# PCB_Board2.net
KiCad netlist of a schematic drawn in Altium Designer
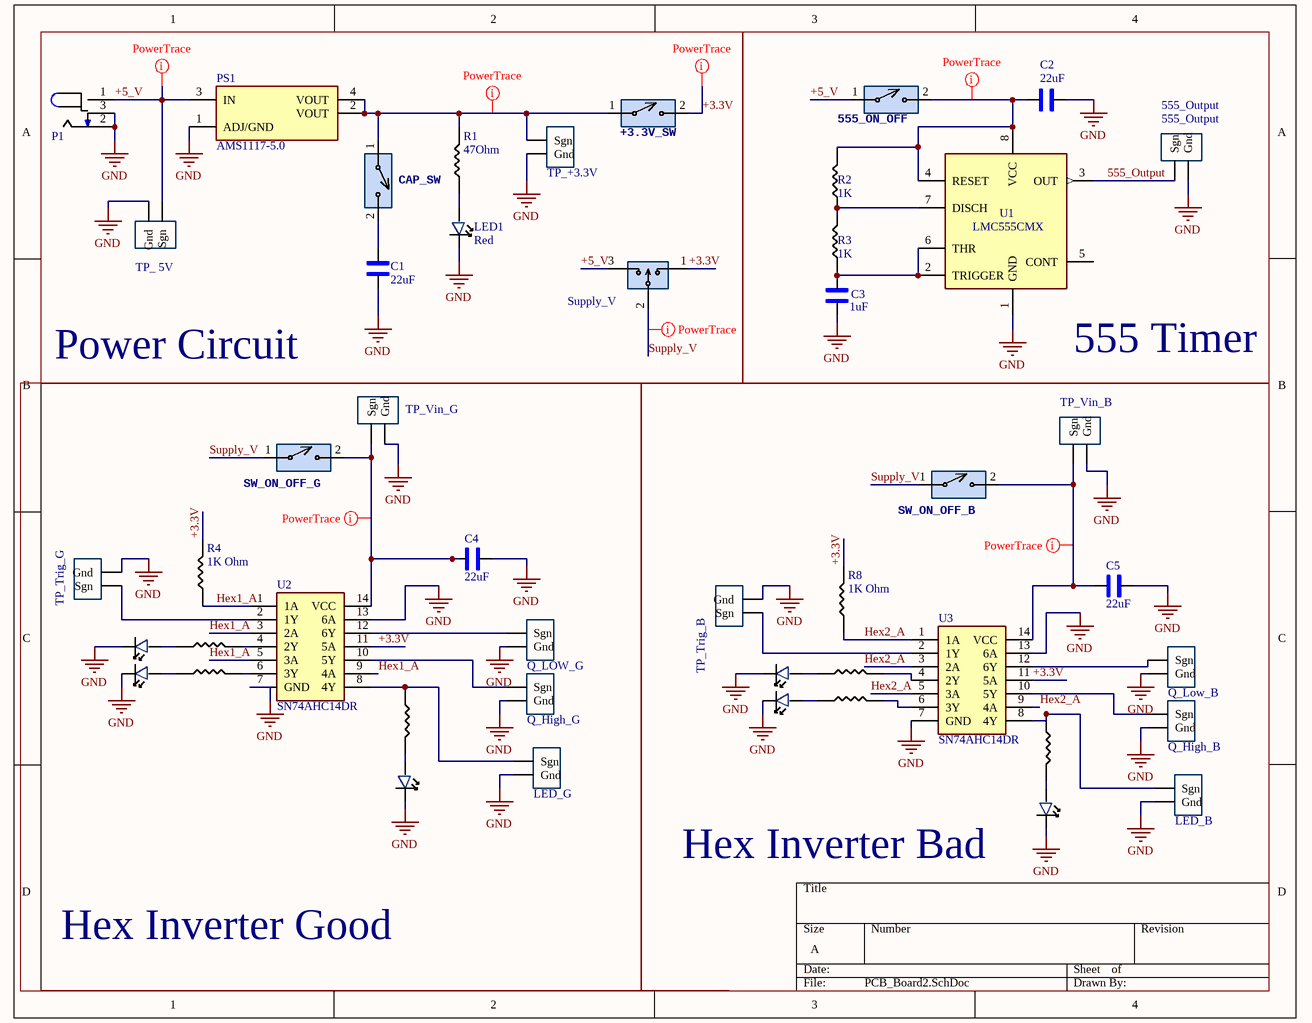
[diagram p0: PCB_Board2.SchDoc]

(export (version "E")
  (design (tool "Eeschema 10.0.6"))
  (components
    (comp (ref "+3.3V_SW")
      (value "SW_2Pin_100mil_Switch")
      (footprint "2Pin-Header-Conn")
      (description "2Pin Header")
      (fields (field (name "LCSC PART#") "C124375"))
      (libsource (lib "ECEN5730Lib_2023_05_DS") (part "SW_2Pin_100mil_Switch"))
    )
    (comp (ref "555_ON_OFF")
      (value "SW_2Pin_100mil_Switch")
      (footprint "2Pin-Header-Conn")
      (description "2Pin Header")
      (fields (field (name "LCSC PART#") "C124375"))
      (libsource (lib "ECEN5730Lib_2023_05_DS") (part "SW_2Pin_100mil_Switch"))
    )
    (comp (ref "555_Output")
      (value "555_Output")
      (footprint "TP10x_Probe")
      (description "Test Point 300 mil centers")
      (libsource (lib "") (part "TP_10x_Probe_2"))
    )
    (comp (ref "C1")
      (value "22uF")
      (footprint "1206_Passive_Capacitor")
      (description "22uF ±10% 25V X5R 1206 Multilayer Ceramic Capacitors MLCC - SMD/SMT RoHS")
      (fields (field (name "MFR PART #") "CL31A226KAHNNNE") (field (name "LCSC PART#") "C12891"))
      (libsource (lib "ECEN5730Lib_2023_05_DS") (part "C_22uF_1206"))
    )
    (comp (ref "C2")
      (value "22uF")
      (footprint "1206_Passive_Capacitor")
      (description "22uF ±10% 25V X5R 1206 Multilayer Ceramic Capacitors MLCC - SMD/SMT RoHS")
      (fields (field (name "MFR PART #") "CL31A226KAHNNNE") (field (name "LCSC PART#") "C12891"))
      (libsource (lib "ECEN5730Lib_2023_05_DS") (part "C_22uF_1206"))
    )
    (comp (ref "C3")
      (value "1uF")
      (footprint "1206_Passive_Capacitor")
      (description "MULTILAYER CERAMIC CAPACITORS MLCC - SMD/SMT 1UF 50V 1206 ROHS")
      (fields (field (name "MFR PART #") "CL31B105KBHNNNE") (field (name "LCSC PART#") "C1848"))
      (libsource (lib "ECEN5730Lib_2023_05_DS") (part "C_1uF_1206"))
    )
    (comp (ref "C4")
      (value "22uF")
      (footprint "1206_Passive_Capacitor")
      (description "22uF ±10% 25V X5R 1206 Multilayer Ceramic Capacitors MLCC - SMD/SMT RoHS")
      (fields (field (name "MFR PART #") "CL31A226KAHNNNE") (field (name "LCSC PART#") "C12891"))
      (libsource (lib "ECEN5730Lib_2023_05_DS") (part "C_22uF_1206"))
    )
    (comp (ref "C5")
      (value "22uF")
      (footprint "1206_Passive_Capacitor")
      (description "22uF ±10% 25V X5R 1206 Multilayer Ceramic Capacitors MLCC - SMD/SMT RoHS")
      (fields (field (name "MFR PART #") "CL31A226KAHNNNE") (field (name "LCSC PART#") "C12891"))
      (libsource (lib "ECEN5730Lib_2023_05_DS") (part "C_22uF_1206"))
    )
    (comp (ref "CAP_SW")
      (value "SW_2Pin_100mil_Switch")
      (footprint "2Pin-Header-Conn")
      (description "2Pin Header")
      (fields (field (name "LCSC PART#") "C124375"))
      (libsource (lib "") (part "SW_2Pin_100mil_Switch_1"))
    )
    (comp (ref "LED1")
      (value "Red")
      (footprint "LED_1206")
      (description "Red 621~631nm 1206 Light Emitting Diodes (LED) RoHS")
      (fields (field (name "MFR PART #") "15-21/R6C-FQ1R1B/2T") (field (name "LCSC PART#") "C93133"))
      (libsource (lib "ECEN5730Lib_2023_05_DS") (part "LED_RED_1206"))
    )
    (comp (ref "LED2")
      (value "Red")
      (footprint "LED_1206")
      (description "Red 621~631nm 1206 Light Emitting Diodes (LED) RoHS")
      (fields (field (name "MFR PART #") "15-21/R6C-FQ1R1B/2T") (field (name "LCSC PART#") "C93133"))
      (libsource (lib "ECEN5730Lib_2023_05_DS") (part "LED_RED_1206"))
    )
    (comp (ref "LED3")
      (value "Red")
      (footprint "LED_1206")
      (description "Red 621~631nm 1206 Light Emitting Diodes (LED) RoHS")
      (fields (field (name "MFR PART #") "15-21/R6C-FQ1R1B/2T") (field (name "LCSC PART#") "C93133"))
      (libsource (lib "ECEN5730Lib_2023_05_DS") (part "LED_RED_1206"))
    )
    (comp (ref "LED4")
      (value "Red")
      (footprint "LED_1206")
      (description "Red 621~631nm 1206 Light Emitting Diodes (LED) RoHS")
      (fields (field (name "MFR PART #") "15-21/R6C-FQ1R1B/2T") (field (name "LCSC PART#") "C93133"))
      (libsource (lib "ECEN5730Lib_2023_05_DS") (part "LED_RED_1206"))
    )
    (comp (ref "LED5")
      (value "Red")
      (footprint "LED_1206")
      (description "Red 621~631nm 1206 Light Emitting Diodes (LED) RoHS")
      (fields (field (name "MFR PART #") "15-21/R6C-FQ1R1B/2T") (field (name "LCSC PART#") "C93133"))
      (libsource (lib "ECEN5730Lib_2023_05_DS") (part "LED_RED_1206"))
    )
    (comp (ref "LED6")
      (value "Red")
      (footprint "LED_1206")
      (description "Red 621~631nm 1206 Light Emitting Diodes (LED) RoHS")
      (fields (field (name "MFR PART #") "15-21/R6C-FQ1R1B/2T") (field (name "LCSC PART#") "C93133"))
      (libsource (lib "ECEN5730Lib_2023_05_DS") (part "LED_RED_1206"))
    )
    (comp (ref "LED7")
      (value "Red")
      (footprint "LED_1206")
      (description "Red 621~631nm 1206 Light Emitting Diodes (LED) RoHS")
      (fields (field (name "MFR PART #") "15-21/R6C-FQ1R1B/2T") (field (name "LCSC PART#") "C93133"))
      (libsource (lib "ECEN5730Lib_2023_05_DS") (part "LED_RED_1206"))
    )
    (comp (ref "LED_B")
      (value "10x Probe TP")
      (footprint "TP10x_Probe")
      (description "Test Point 300 mil centers")
      (libsource (lib "ECEN5730Lib_2023_05_DS") (part "TP_10x_Probe"))
    )
    (comp (ref "LED_G")
      (value "10x Probe TP")
      (footprint "TP10x_Probe")
      (description "Test Point 300 mil centers")
      (libsource (lib "ECEN5730Lib_2023_05_DS") (part "TP_10x_Probe"))
    )
    (comp (ref "P1")
      (value "Power Jack")
      (footprint "Power_Jack")
      (description "Power Barrel Connector Jack 2.10mm ID (0.083\"), 5.50mm OD (0.217\") Through Hole, Right Angle")
      (fields (field (name "MFR PART #") "PJ-102A") (field (name "LCSC PART#") "C136744"))
      (libsource (lib "ECEN5730Lib_2023_05_DS") (part "P_Power Jack"))
    )
    (comp (ref "PS1")
      (value "AMS1117-5.0")
      (footprint "LDO")
      (description "LOW DROPOUT REGULATORS(LDO) POSITIVE FIXED 1.3V @ 1A 15V 5V 1A SOT-223 ROHS")
      (fields (field (name "LCSC PART#") "C6187"))
      (libsource (lib "ECEN5730Lib_2023_05_DS") (part "PS_AMS_LDO_5V"))
    )
    (comp (ref "Q_High_B")
      (value "10x Probe TP")
      (footprint "TP10x_Probe")
      (description "Test Point 300 mil centers")
      (libsource (lib "ECEN5730Lib_2023_05_DS") (part "TP_10x_Probe"))
    )
    (comp (ref "Q_High_G")
      (value "10x Probe TP")
      (footprint "TP10x_Probe")
      (description "Test Point 300 mil centers")
      (libsource (lib "ECEN5730Lib_2023_05_DS") (part "TP_10x_Probe"))
    )
    (comp (ref "Q_Low_B")
      (value "10x Probe TP")
      (footprint "TP10x_Probe")
      (description "Test Point 300 mil centers")
      (libsource (lib "ECEN5730Lib_2023_05_DS") (part "TP_10x_Probe"))
    )
    (comp (ref "Q_LOW_G")
      (value "10x Probe TP")
      (footprint "TP10x_Probe")
      (description "Test Point 300 mil centers")
      (libsource (lib "ECEN5730Lib_2023_05_DS") (part "TP_10x_Probe"))
    )
    (comp (ref "R1")
      (value "47Ohm")
      (footprint "1206_Passive_Resitor")
      (description "47Ω ±5% 0.25W ±200ppm/℃ 1206 Chip Resistor - Surface Mount RoHS")
      (fields (field (name "MFR PART #") "1206W4J0470T5E") (field (name "LCSC PART#") "C25384"))
      (libsource (lib "ECEN5730Lib_2023_05_DS") (part "R_47Ohm_1206"))
    )
    (comp (ref "R2")
      (value "1K")
      (footprint "1206_Passive_Resitor")
      (description "CHIP RESISTOR - SURFACE MOUNT 1KOHMS ±1% 1/4W 1206 ROHS")
      (fields (field (name "MFR PART #") "RNCP1206FTD1K00CT") (field (name "LCSC PART#") "C4410"))
      (libsource (lib "ECEN5730Lib_2023_05_DS") (part "R_1K_1206"))
    )
    (comp (ref "R3")
      (value "1K")
      (footprint "1206_Passive_Resitor")
      (description "CHIP RESISTOR - SURFACE MOUNT 1KOHMS ±1% 1/4W 1206 ROHS")
      (fields (field (name "MFR PART #") "RNCP1206FTD1K00CT") (field (name "LCSC PART#") "C4410"))
      (libsource (lib "ECEN5730Lib_2023_05_DS") (part "R_1K_1206"))
    )
    (comp (ref "R4")
      (value "1K Ohm")
      (footprint "1206_Passive_Resitor")
      (description "CHIP RESISTOR - SURFACE MOUNT 1KOHMS ±1% 1/4W 1206 ROHS")
      (fields (field (name "MFR PART #") "RNCP1206FTD1K00CT") (field (name "LCSC PART#") "C4410"))
      (libsource (lib "ECEN5730Lib_2023_05_DS") (part "R_1K_1206"))
    )
    (comp (ref "R5")
      (value "2Ohm")
      (footprint "1206_Passive_Resitor")
      (description "2Ω ±1% 0.25W ±400ppm/℃ 1206 Chip Resistor - Surface Mount RoHS")
      (fields (field (name "MFR PART #") "1206W4F200KT5E") (field (name "LCSC PART#") "C17942"))
      (libsource (lib "ECEN5730Lib_2023_05_DS") (part "R_2Ohm_1206"))
    )
    (comp (ref "R6")
      (value "2Ohm")
      (footprint "1206_Passive_Resitor")
      (description "2Ω ±1% 0.25W ±400ppm/℃ 1206 Chip Resistor - Surface Mount RoHS")
      (fields (field (name "MFR PART #") "1206W4F200KT5E") (field (name "LCSC PART#") "C17942"))
      (libsource (lib "ECEN5730Lib_2023_05_DS") (part "R_2Ohm_1206"))
    )
    (comp (ref "R7")
      (value "2Ohm")
      (footprint "1206_Passive_Resitor")
      (description "2Ω ±1% 0.25W ±400ppm/℃ 1206 Chip Resistor - Surface Mount RoHS")
      (fields (field (name "MFR PART #") "1206W4F200KT5E") (field (name "LCSC PART#") "C17942"))
      (libsource (lib "ECEN5730Lib_2023_05_DS") (part "R_2Ohm_1206"))
    )
    (comp (ref "R8")
      (value "1K Ohm")
      (footprint "1206_Passive_Resitor")
      (description "CHIP RESISTOR - SURFACE MOUNT 1KOHMS ±1% 1/4W 1206 ROHS")
      (fields (field (name "MFR PART #") "RNCP1206FTD1K00CT") (field (name "LCSC PART#") "C4410"))
      (libsource (lib "ECEN5730Lib_2023_05_DS") (part "R_1K_1206"))
    )
    (comp (ref "R9")
      (value "2Ohm")
      (footprint "1206_Passive_Resitor")
      (description "2Ω ±1% 0.25W ±400ppm/℃ 1206 Chip Resistor - Surface Mount RoHS")
      (fields (field (name "MFR PART #") "1206W4F200KT5E") (field (name "LCSC PART#") "C17942"))
      (libsource (lib "ECEN5730Lib_2023_05_DS") (part "R_2Ohm_1206"))
    )
    (comp (ref "R10")
      (value "2Ohm")
      (footprint "1206_Passive_Resitor")
      (description "2Ω ±1% 0.25W ±400ppm/℃ 1206 Chip Resistor - Surface Mount RoHS")
      (fields (field (name "MFR PART #") "1206W4F200KT5E") (field (name "LCSC PART#") "C17942"))
      (libsource (lib "ECEN5730Lib_2023_05_DS") (part "R_2Ohm_1206"))
    )
    (comp (ref "R11")
      (value "2Ohm")
      (footprint "1206_Passive_Resitor")
      (description "2Ω ±1% 0.25W ±400ppm/℃ 1206 Chip Resistor - Surface Mount RoHS")
      (fields (field (name "MFR PART #") "1206W4F200KT5E") (field (name "LCSC PART#") "C17942"))
      (libsource (lib "ECEN5730Lib_2023_05_DS") (part "R_2Ohm_1206"))
    )
    (comp (ref "Supply_V")
      (value "PREC003SAAN-RC")
      (footprint "3_PIN_100mil")
      (description "Connector Header Through Hole 3 position 0.100\" (2.54mm)")
      (fields (field (name "LCSC PART#") "C49257"))
      (libsource (lib "ECEN5730Lib_2023_05_DS") (part "SW_3Pin_100mil_Switch"))
    )
    (comp (ref "SW_ON_OFF_B")
      (value "SW_2Pin_100mil_Switch")
      (footprint "2Pin-Header-Conn")
      (description "2Pin Header")
      (fields (field (name "LCSC PART#") "C124375"))
      (libsource (lib "ECEN5730Lib_2023_05_DS") (part "SW_2Pin_100mil_Switch"))
    )
    (comp (ref "SW_ON_OFF_G")
      (value "SW_2Pin_100mil_Switch")
      (footprint "2Pin-Header-Conn")
      (description "2Pin Header")
      (fields (field (name "LCSC PART#") "C124375"))
      (libsource (lib "ECEN5730Lib_2023_05_DS") (part "SW_2Pin_100mil_Switch"))
    )
    (comp (ref "TP_ 5V")
      (value "10x Probe TP")
      (footprint "TP10x_Probe")
      (description "Test Point 300 mil centers")
      (libsource (lib "") (part "TP_10x_Probe_1"))
    )
    (comp (ref "TP_+3.3V")
      (value "10x Probe TP")
      (footprint "TP10x_Probe")
      (description "Test Point 300 mil centers")
      (libsource (lib "ECEN5730Lib_2023_05_DS") (part "TP_10x_Probe"))
    )
    (comp (ref "TP_Trig_B")
      (value "10x Probe TP")
      (footprint "TP10x_Probe")
      (description "Test Point 300 mil centers")
      (libsource (lib "") (part "TP_10x_Probe_3"))
    )
    (comp (ref "TP_Trig_G")
      (value "10x Probe TP")
      (footprint "TP10x_Probe")
      (description "Test Point 300 mil centers")
      (libsource (lib "") (part "TP_10x_Probe_3"))
    )
    (comp (ref "TP_Vin_B")
      (value "10x Probe TP")
      (footprint "TP10x_Probe")
      (description "Test Point 300 mil centers")
      (libsource (lib "") (part "TP_10x_Probe_2"))
    )
    (comp (ref "TP_Vin_G")
      (value "10x Probe TP")
      (footprint "TP10x_Probe")
      (description "Test Point 300 mil centers")
      (libsource (lib "") (part "TP_10x_Probe_2"))
    )
    (comp (ref "U1")
      (value "LMC555CMX")
      (footprint "TS555IDTTR")
      (description "555 Type, Timer/Oscillator _Single_ IC 3MHz 8-SO")
      (fields (field (name "MFR PART #") "LMC555CMX/NOPB") (field (name "LCSC PART#") "C90760"))
      (libsource (lib "ECEN5730Lib_2023_05_DS") (part "U_555_Fast"))
    )
    (comp (ref "U2")
      (value "SN74AHC14DR")
      (footprint "HEX_74AC14")
      (description "Inverter IC 6 Channel Schmitt Trigger 14-SOIC")
      (fields (field (name "LCSC PART#") "C6942"))
      (libsource (lib "ECEN5730Lib_2023_05_DS") (part "U_74AHC14"))
    )
    (comp (ref "U3")
      (value "SN74AHC14DR")
      (footprint "HEX_74AC14")
      (description "Inverter IC 6 Channel Schmitt Trigger 14-SOIC")
      (fields (field (name "LCSC PART#") "C6942"))
      (libsource (lib "ECEN5730Lib_2023_05_DS") (part "U_74AHC14"))
    )
  )
  (nets
    (net (code "1") (name "/+3.3V") (class "Default")
      (node (ref "+3.3V_SW") (pin "2") (pinfunction "2_2") (pintype "passive"))
      (node (ref "R4") (pin "2") (pinfunction "2_2") (pintype "passive"))
      (node (ref "R8") (pin "2") (pinfunction "2_2") (pintype "passive"))
      (node (ref "Supply_V") (pin "1") (pinfunction "1_1") (pintype "passive"))
      (node (ref "U2") (pin "11") (pinfunction "5A_11") (pintype "passive"))
      (node (ref "U3") (pin "11") (pinfunction "5A_11") (pintype "passive"))
    )
    (net (code "2") (name "/+5_V") (class "Default")
      (node (ref "555_ON_OFF") (pin "1") (pinfunction "1_1") (pintype "passive"))
      (node (ref "P1") (pin "1") (pinfunction "1_1") (pintype "power_in"))
      (node (ref "PS1") (pin "3") (pinfunction "IN_3") (pintype "power_in"))
      (node (ref "Supply_V") (pin "3") (pinfunction "3_3") (pintype "passive"))
      (node (ref "TP_ 5V") (pin "1") (pinfunction "Sgn_1") (pintype "passive"))
    )
    (net (code "3") (name "/555_Output") (class "Default")
      (node (ref "555_Output") (pin "1") (pinfunction "Sgn_1") (pintype "passive"))
      (node (ref "U1") (pin "3") (pinfunction "OUT_3") (pintype "output"))
    )
    (net (code "4") (name "/Hex1_A") (class "Default")
      (node (ref "R4") (pin "1") (pinfunction "1_1") (pintype "passive"))
      (node (ref "U2") (pin "1") (pinfunction "1A_1") (pintype "passive"))
      (node (ref "U2") (pin "3") (pinfunction "2A_3") (pintype "passive"))
      (node (ref "U2") (pin "5") (pinfunction "3A_5") (pintype "passive"))
      (node (ref "U2") (pin "9") (pinfunction "4A_9") (pintype "passive"))
    )
    (net (code "5") (name "/Hex2_A") (class "Default")
      (node (ref "R8") (pin "1") (pinfunction "1_1") (pintype "passive"))
      (node (ref "U3") (pin "1") (pinfunction "1A_1") (pintype "passive"))
      (node (ref "U3") (pin "3") (pinfunction "2A_3") (pintype "passive"))
      (node (ref "U3") (pin "5") (pinfunction "3A_5") (pintype "passive"))
      (node (ref "U3") (pin "9") (pinfunction "4A_9") (pintype "passive"))
    )
    (net (code "6") (name "/Supply_V") (class "Default")
      (node (ref "SW_ON_OFF_B") (pin "1") (pinfunction "1_1") (pintype "passive"))
      (node (ref "SW_ON_OFF_G") (pin "1") (pinfunction "1_1") (pintype "passive"))
      (node (ref "Supply_V") (pin "2") (pinfunction "2_2") (pintype "passive"))
    )
    (net (code "7") (name "GND") (class "Default")
      (node (ref "555_Output") (pin "2") (pinfunction "Gnd_2") (pintype "passive"))
      (node (ref "C1") (pin "1") (pinfunction "1_1") (pintype "passive"))
      (node (ref "C2") (pin "2") (pinfunction "2_2") (pintype "passive"))
      (node (ref "C3") (pin "2") (pinfunction "2_2") (pintype "passive"))
      (node (ref "C4") (pin "1") (pinfunction "1_1") (pintype "passive"))
      (node (ref "C5") (pin "1") (pinfunction "1_1") (pintype "passive"))
      (node (ref "LED1") (pin "2") (pinfunction "2_2") (pintype "passive"))
      (node (ref "LED2") (pin "2") (pinfunction "2_2") (pintype "passive"))
      (node (ref "LED3") (pin "2") (pinfunction "2_2") (pintype "passive"))
      (node (ref "LED4") (pin "2") (pinfunction "2_2") (pintype "passive"))
      (node (ref "LED5") (pin "2") (pinfunction "2_2") (pintype "passive"))
      (node (ref "LED6") (pin "2") (pinfunction "2_2") (pintype "passive"))
      (node (ref "LED7") (pin "2") (pinfunction "2_2") (pintype "passive"))
      (node (ref "LED_B") (pin "2") (pinfunction "Gnd_2") (pintype "passive"))
      (node (ref "LED_G") (pin "2") (pinfunction "Gnd_2") (pintype "passive"))
      (node (ref "P1") (pin "2") (pinfunction "2_2") (pintype "power_in"))
      (node (ref "P1") (pin "3") (pinfunction "3_3") (pintype "power_in"))
      (node (ref "PS1") (pin "1") (pinfunction "ADJ/GND_1") (pintype "passive"))
      (node (ref "Q_High_B") (pin "2") (pinfunction "Gnd_2") (pintype "passive"))
      (node (ref "Q_High_G") (pin "2") (pinfunction "Gnd_2") (pintype "passive"))
      (node (ref "Q_LOW_G") (pin "2") (pinfunction "Gnd_2") (pintype "passive"))
      (node (ref "Q_Low_B") (pin "2") (pinfunction "Gnd_2") (pintype "passive"))
      (node (ref "TP_ 5V") (pin "2") (pinfunction "Gnd_2") (pintype "passive"))
      (node (ref "TP_+3.3V") (pin "2") (pinfunction "Gnd_2") (pintype "passive"))
      (node (ref "TP_Trig_B") (pin "2") (pinfunction "Gnd_2") (pintype "passive"))
      (node (ref "TP_Trig_G") (pin "2") (pinfunction "Gnd_2") (pintype "passive"))
      (node (ref "TP_Vin_B") (pin "2") (pinfunction "Gnd_2") (pintype "passive"))
      (node (ref "TP_Vin_G") (pin "2") (pinfunction "Gnd_2") (pintype "passive"))
      (node (ref "U1") (pin "1") (pinfunction "GND_1") (pintype "power_in"))
      (node (ref "U2") (pin "13") (pinfunction "6A_13") (pintype "passive"))
      (node (ref "U2") (pin "7") (pinfunction "GND_7") (pintype "passive"))
      (node (ref "U3") (pin "13") (pinfunction "6A_13") (pintype "passive"))
      (node (ref "U3") (pin "7") (pinfunction "GND_7") (pintype "passive"))
    )
    (net (code "8") (name "Net-(C1-Pad2)") (class "Default")
      (node (ref "C1") (pin "2") (pinfunction "2_2") (pintype "passive"))
      (node (ref "CAP_SW") (pin "2") (pinfunction "2_2") (pintype "passive"))
    )
    (net (code "9") (name "Net-(LED1-Pad1)") (class "Default")
      (node (ref "LED1") (pin "1") (pinfunction "1_1") (pintype "passive"))
      (node (ref "R1") (pin "1") (pinfunction "1_1") (pintype "passive"))
    )
    (net (code "10") (name "Net-(LED2-Pad1)") (class "Default")
      (node (ref "LED2") (pin "1") (pinfunction "1_1") (pintype "passive"))
      (node (ref "R5") (pin "1") (pinfunction "1_1") (pintype "passive"))
    )
    (net (code "11") (name "Net-(LED3-Pad1)") (class "Default")
      (node (ref "LED3") (pin "1") (pinfunction "1_1") (pintype "passive"))
      (node (ref "R6") (pin "1") (pinfunction "1_1") (pintype "passive"))
    )
    (net (code "12") (name "Net-(LED4-Pad1)") (class "Default")
      (node (ref "LED4") (pin "1") (pinfunction "1_1") (pintype "passive"))
      (node (ref "R7") (pin "2") (pinfunction "2_2") (pintype "passive"))
    )
    (net (code "13") (name "Net-(LED5-Pad1)") (class "Default")
      (node (ref "LED5") (pin "1") (pinfunction "1_1") (pintype "passive"))
      (node (ref "R9") (pin "1") (pinfunction "1_1") (pintype "passive"))
    )
    (net (code "14") (name "Net-(LED6-Pad1)") (class "Default")
      (node (ref "LED6") (pin "1") (pinfunction "1_1") (pintype "passive"))
      (node (ref "R10") (pin "1") (pinfunction "1_1") (pintype "passive"))
    )
    (net (code "15") (name "Net-(LED7-Pad1)") (class "Default")
      (node (ref "LED7") (pin "1") (pinfunction "1_1") (pintype "passive"))
      (node (ref "R11") (pin "2") (pinfunction "2_2") (pintype "passive"))
    )
    (net (code "16") (name "Net-(LED_B-Sgn)") (class "Default")
      (node (ref "LED_B") (pin "1") (pinfunction "Sgn_1") (pintype "passive"))
      (node (ref "R11") (pin "1") (pinfunction "1_1") (pintype "passive"))
      (node (ref "U3") (pin "8") (pinfunction "4Y_8") (pintype "passive"))
    )
    (net (code "17") (name "Net-(LED_G-Sgn)") (class "Default")
      (node (ref "LED_G") (pin "1") (pinfunction "Sgn_1") (pintype "passive"))
      (node (ref "R7") (pin "1") (pinfunction "1_1") (pintype "passive"))
      (node (ref "U2") (pin "8") (pinfunction "4Y_8") (pintype "passive"))
    )
    (net (code "18") (name "Net-(Q_High_B-Sgn)") (class "Default")
      (node (ref "Q_High_B") (pin "1") (pinfunction "Sgn_1") (pintype "passive"))
      (node (ref "U3") (pin "10") (pinfunction "5Y_10") (pintype "passive"))
    )
    (net (code "19") (name "Net-(Q_High_G-Sgn)") (class "Default")
      (node (ref "Q_High_G") (pin "1") (pinfunction "Sgn_1") (pintype "passive"))
      (node (ref "U2") (pin "10") (pinfunction "5Y_10") (pintype "passive"))
    )
    (net (code "20") (name "Net-(Q_LOW_G-Sgn)") (class "Default")
      (node (ref "Q_LOW_G") (pin "1") (pinfunction "Sgn_1") (pintype "passive"))
      (node (ref "U2") (pin "12") (pinfunction "6Y_12") (pintype "passive"))
    )
    (net (code "21") (name "Net-(Q_Low_B-Sgn)") (class "Default")
      (node (ref "Q_Low_B") (pin "1") (pinfunction "Sgn_1") (pintype "passive"))
      (node (ref "U3") (pin "12") (pinfunction "6Y_12") (pintype "passive"))
    )
    (net (code "22") (name "Net-(TP_+3.3V-Sgn)") (class "Default")
      (node (ref "+3.3V_SW") (pin "1") (pinfunction "1_1") (pintype "passive"))
      (node (ref "CAP_SW") (pin "1") (pinfunction "1_1") (pintype "passive"))
      (node (ref "PS1") (pin "2") (pinfunction "VOUT_2") (pintype "power_in"))
      (node (ref "PS1") (pin "4") (pinfunction "VOUT_4") (pintype "power_in"))
      (node (ref "R1") (pin "2") (pinfunction "2_2") (pintype "passive"))
      (node (ref "TP_+3.3V") (pin "1") (pinfunction "Sgn_1") (pintype "passive"))
    )
    (net (code "23") (name "Net-(TP_Trig_B-Sgn)") (class "Default")
      (node (ref "TP_Trig_B") (pin "1") (pinfunction "Sgn_1") (pintype "passive"))
      (node (ref "U3") (pin "2") (pinfunction "1Y_2") (pintype "passive"))
    )
    (net (code "24") (name "Net-(TP_Trig_G-Sgn)") (class "Default")
      (node (ref "TP_Trig_G") (pin "1") (pinfunction "Sgn_1") (pintype "passive"))
      (node (ref "U2") (pin "2") (pinfunction "1Y_2") (pintype "passive"))
    )
    (net (code "25") (name "Net-(TP_Vin_B-Sgn)") (class "Default")
      (node (ref "C5") (pin "2") (pinfunction "2_2") (pintype "passive"))
      (node (ref "SW_ON_OFF_B") (pin "2") (pinfunction "2_2") (pintype "passive"))
      (node (ref "TP_Vin_B") (pin "1") (pinfunction "Sgn_1") (pintype "passive"))
      (node (ref "U3") (pin "14") (pinfunction "VCC_14") (pintype "passive"))
    )
    (net (code "26") (name "Net-(TP_Vin_G-Sgn)") (class "Default")
      (node (ref "C4") (pin "2") (pinfunction "2_2") (pintype "passive"))
      (node (ref "SW_ON_OFF_G") (pin "2") (pinfunction "2_2") (pintype "passive"))
      (node (ref "TP_Vin_G") (pin "1") (pinfunction "Sgn_1") (pintype "passive"))
      (node (ref "U2") (pin "14") (pinfunction "VCC_14") (pintype "passive"))
    )
    (net (code "27") (name "Net-(U1-DISCH)") (class "Default")
      (node (ref "R2") (pin "1") (pinfunction "1_1") (pintype "passive"))
      (node (ref "R3") (pin "2") (pinfunction "2_2") (pintype "passive"))
      (node (ref "U1") (pin "7") (pinfunction "DISCH_7") (pintype "passive"))
    )
    (net (code "28") (name "Net-(U1-RESET)") (class "Default")
      (node (ref "555_ON_OFF") (pin "2") (pinfunction "2_2") (pintype "passive"))
      (node (ref "C2") (pin "1") (pinfunction "1_1") (pintype "passive"))
      (node (ref "R2") (pin "2") (pinfunction "2_2") (pintype "passive"))
      (node (ref "U1") (pin "4") (pinfunction "RESET_4") (pintype "passive"))
      (node (ref "U1") (pin "8") (pinfunction "VCC_8") (pintype "power_in"))
    )
    (net (code "29") (name "Net-(U1-THR)") (class "Default")
      (node (ref "C3") (pin "1") (pinfunction "1_1") (pintype "passive"))
      (node (ref "R3") (pin "1") (pinfunction "1_1") (pintype "passive"))
      (node (ref "U1") (pin "2") (pinfunction "TRIGGER_2") (pintype "passive"))
      (node (ref "U1") (pin "6") (pinfunction "THR_6") (pintype "passive"))
    )
    (net (code "30") (name "Net-(U2-2Y)") (class "Default")
      (node (ref "R5") (pin "2") (pinfunction "2_2") (pintype "passive"))
      (node (ref "U2") (pin "4") (pinfunction "2Y_4") (pintype "passive"))
    )
    (net (code "31") (name "Net-(U2-3Y)") (class "Default")
      (node (ref "R6") (pin "2") (pinfunction "2_2") (pintype "passive"))
      (node (ref "U2") (pin "6") (pinfunction "3Y_6") (pintype "passive"))
    )
    (net (code "32") (name "Net-(U3-2Y)") (class "Default")
      (node (ref "R9") (pin "2") (pinfunction "2_2") (pintype "passive"))
      (node (ref "U3") (pin "4") (pinfunction "2Y_4") (pintype "passive"))
    )
    (net (code "33") (name "Net-(U3-3Y)") (class "Default")
      (node (ref "R10") (pin "2") (pinfunction "2_2") (pintype "passive"))
      (node (ref "U3") (pin "6") (pinfunction "3Y_6") (pintype "passive"))
    )
    (net (code "34") (name "unconnected-(U1-CONT-Pad5)") (class "Default")
      (node (ref "U1") (pin "5") (pinfunction "CONT_5") (pintype "passive"))
    )
  )
)
